# bru-breakout.net
KiCad netlist of a schematic drawn in EAGLE
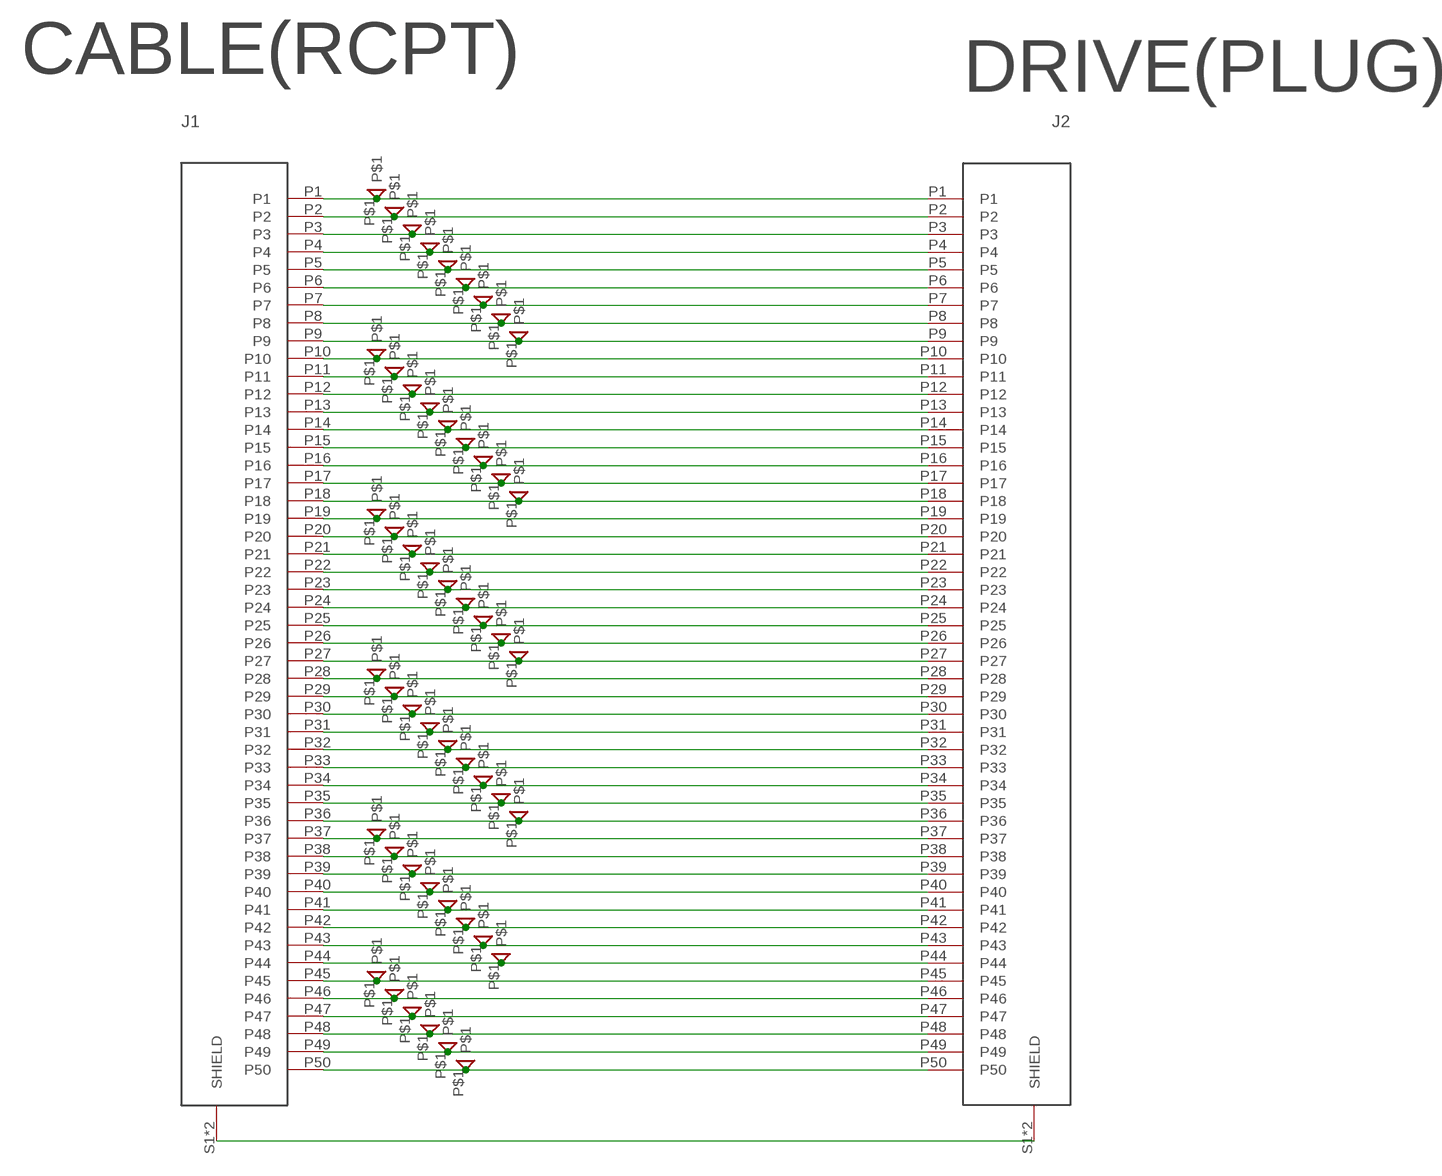
[diagram p0: schematic, sheet 1]

(export (version "E")
  (design (tool "Eeschema 10.0.6"))
  (components
    (comp (ref "J1")
      (value "3M_10250-55H3PC(RECEPTACLE)")
      (footprint "eagle-import:3M_10250-55H3PC(RECEPTACLE)")
      (libsource (lib "eagle-import") (part "3M_10250-55H3PC(RECEPTACLE)"))
    )
    (comp (ref "J2")
      (value "3M_10150-52E2PC(PLUG)")
      (footprint "eagle-import:3M_10150-52E2PC(PLUG)")
      (libsource (lib "eagle-import") (part "3M_10150-52E2PC(PLUG)"))
    )
    (comp (ref "U$1")
      (value "PTH_SMALL")
      (footprint "eagle-import:PTH_SMALL")
      (libsource (lib "eagle-import") (part "PTH_SMALL"))
    )
    (comp (ref "U$2")
      (value "PTH_SMALL")
      (footprint "eagle-import:PTH_SMALL")
      (libsource (lib "eagle-import") (part "PTH_SMALL"))
    )
    (comp (ref "U$3")
      (value "PTH_SMALL")
      (footprint "eagle-import:PTH_SMALL")
      (libsource (lib "eagle-import") (part "PTH_SMALL"))
    )
    (comp (ref "U$4")
      (value "PTH_SMALL")
      (footprint "eagle-import:PTH_SMALL")
      (libsource (lib "eagle-import") (part "PTH_SMALL"))
    )
    (comp (ref "U$5")
      (value "PTH_SMALL")
      (footprint "eagle-import:PTH_SMALL")
      (libsource (lib "eagle-import") (part "PTH_SMALL"))
    )
    (comp (ref "U$6")
      (value "PTH_SMALL")
      (footprint "eagle-import:PTH_SMALL")
      (libsource (lib "eagle-import") (part "PTH_SMALL"))
    )
    (comp (ref "U$7")
      (value "PTH_SMALL")
      (footprint "eagle-import:PTH_SMALL")
      (libsource (lib "eagle-import") (part "PTH_SMALL"))
    )
    (comp (ref "U$8")
      (value "PTH_SMALL")
      (footprint "eagle-import:PTH_SMALL")
      (libsource (lib "eagle-import") (part "PTH_SMALL"))
    )
    (comp (ref "U$9")
      (value "PTH_SMALL")
      (footprint "eagle-import:PTH_SMALL")
      (libsource (lib "eagle-import") (part "PTH_SMALL"))
    )
    (comp (ref "U$10")
      (value "PTH_SMALL")
      (footprint "eagle-import:PTH_SMALL")
      (libsource (lib "eagle-import") (part "PTH_SMALL"))
    )
    (comp (ref "U$11")
      (value "PTH_SMALL")
      (footprint "eagle-import:PTH_SMALL")
      (libsource (lib "eagle-import") (part "PTH_SMALL"))
    )
    (comp (ref "U$12")
      (value "PTH_SMALL")
      (footprint "eagle-import:PTH_SMALL")
      (libsource (lib "eagle-import") (part "PTH_SMALL"))
    )
    (comp (ref "U$13")
      (value "PTH_SMALL")
      (footprint "eagle-import:PTH_SMALL")
      (libsource (lib "eagle-import") (part "PTH_SMALL"))
    )
    (comp (ref "U$14")
      (value "PTH_SMALL")
      (footprint "eagle-import:PTH_SMALL")
      (libsource (lib "eagle-import") (part "PTH_SMALL"))
    )
    (comp (ref "U$15")
      (value "PTH_SMALL")
      (footprint "eagle-import:PTH_SMALL")
      (libsource (lib "eagle-import") (part "PTH_SMALL"))
    )
    (comp (ref "U$16")
      (value "PTH_SMALL")
      (footprint "eagle-import:PTH_SMALL")
      (libsource (lib "eagle-import") (part "PTH_SMALL"))
    )
    (comp (ref "U$17")
      (value "PTH_SMALL")
      (footprint "eagle-import:PTH_SMALL")
      (libsource (lib "eagle-import") (part "PTH_SMALL"))
    )
    (comp (ref "U$18")
      (value "PTH_SMALL")
      (footprint "eagle-import:PTH_SMALL")
      (libsource (lib "eagle-import") (part "PTH_SMALL"))
    )
    (comp (ref "U$19")
      (value "PTH_SMALL")
      (footprint "eagle-import:PTH_SMALL")
      (libsource (lib "eagle-import") (part "PTH_SMALL"))
    )
    (comp (ref "U$20")
      (value "PTH_SMALL")
      (footprint "eagle-import:PTH_SMALL")
      (libsource (lib "eagle-import") (part "PTH_SMALL"))
    )
    (comp (ref "U$21")
      (value "PTH_SMALL")
      (footprint "eagle-import:PTH_SMALL")
      (libsource (lib "eagle-import") (part "PTH_SMALL"))
    )
    (comp (ref "U$22")
      (value "PTH_SMALL")
      (footprint "eagle-import:PTH_SMALL")
      (libsource (lib "eagle-import") (part "PTH_SMALL"))
    )
    (comp (ref "U$23")
      (value "PTH_SMALL")
      (footprint "eagle-import:PTH_SMALL")
      (libsource (lib "eagle-import") (part "PTH_SMALL"))
    )
    (comp (ref "U$24")
      (value "PTH_SMALL")
      (footprint "eagle-import:PTH_SMALL")
      (libsource (lib "eagle-import") (part "PTH_SMALL"))
    )
    (comp (ref "U$25")
      (value "PTH_SMALL")
      (footprint "eagle-import:PTH_SMALL")
      (libsource (lib "eagle-import") (part "PTH_SMALL"))
    )
    (comp (ref "U$26")
      (value "PTH_SMALL")
      (footprint "eagle-import:PTH_SMALL")
      (libsource (lib "eagle-import") (part "PTH_SMALL"))
    )
    (comp (ref "U$27")
      (value "PTH_SMALL")
      (footprint "eagle-import:PTH_SMALL")
      (libsource (lib "eagle-import") (part "PTH_SMALL"))
    )
    (comp (ref "U$28")
      (value "PTH_SMALL")
      (footprint "eagle-import:PTH_SMALL")
      (libsource (lib "eagle-import") (part "PTH_SMALL"))
    )
    (comp (ref "U$29")
      (value "PTH_SMALL")
      (footprint "eagle-import:PTH_SMALL")
      (libsource (lib "eagle-import") (part "PTH_SMALL"))
    )
    (comp (ref "U$30")
      (value "PTH_SMALL")
      (footprint "eagle-import:PTH_SMALL")
      (libsource (lib "eagle-import") (part "PTH_SMALL"))
    )
    (comp (ref "U$31")
      (value "PTH_SMALL")
      (footprint "eagle-import:PTH_SMALL")
      (libsource (lib "eagle-import") (part "PTH_SMALL"))
    )
    (comp (ref "U$32")
      (value "PTH_SMALL")
      (footprint "eagle-import:PTH_SMALL")
      (libsource (lib "eagle-import") (part "PTH_SMALL"))
    )
    (comp (ref "U$33")
      (value "PTH_SMALL")
      (footprint "eagle-import:PTH_SMALL")
      (libsource (lib "eagle-import") (part "PTH_SMALL"))
    )
    (comp (ref "U$34")
      (value "PTH_SMALL")
      (footprint "eagle-import:PTH_SMALL")
      (libsource (lib "eagle-import") (part "PTH_SMALL"))
    )
    (comp (ref "U$35")
      (value "PTH_SMALL")
      (footprint "eagle-import:PTH_SMALL")
      (libsource (lib "eagle-import") (part "PTH_SMALL"))
    )
    (comp (ref "U$36")
      (value "PTH_SMALL")
      (footprint "eagle-import:PTH_SMALL")
      (libsource (lib "eagle-import") (part "PTH_SMALL"))
    )
    (comp (ref "U$37")
      (value "PTH_SMALL")
      (footprint "eagle-import:PTH_SMALL")
      (libsource (lib "eagle-import") (part "PTH_SMALL"))
    )
    (comp (ref "U$38")
      (value "PTH_SMALL")
      (footprint "eagle-import:PTH_SMALL")
      (libsource (lib "eagle-import") (part "PTH_SMALL"))
    )
    (comp (ref "U$39")
      (value "PTH_SMALL")
      (footprint "eagle-import:PTH_SMALL")
      (libsource (lib "eagle-import") (part "PTH_SMALL"))
    )
    (comp (ref "U$40")
      (value "PTH_SMALL")
      (footprint "eagle-import:PTH_SMALL")
      (libsource (lib "eagle-import") (part "PTH_SMALL"))
    )
    (comp (ref "U$41")
      (value "PTH_SMALL")
      (footprint "eagle-import:PTH_SMALL")
      (libsource (lib "eagle-import") (part "PTH_SMALL"))
    )
    (comp (ref "U$42")
      (value "PTH_SMALL")
      (footprint "eagle-import:PTH_SMALL")
      (libsource (lib "eagle-import") (part "PTH_SMALL"))
    )
    (comp (ref "U$43")
      (value "PTH_SMALL")
      (footprint "eagle-import:PTH_SMALL")
      (libsource (lib "eagle-import") (part "PTH_SMALL"))
    )
    (comp (ref "U$44")
      (value "PTH_SMALL")
      (footprint "eagle-import:PTH_SMALL")
      (libsource (lib "eagle-import") (part "PTH_SMALL"))
    )
    (comp (ref "U$45")
      (value "PTH_SMALL")
      (footprint "eagle-import:PTH_SMALL")
      (libsource (lib "eagle-import") (part "PTH_SMALL"))
    )
    (comp (ref "U$46")
      (value "PTH_SMALL")
      (footprint "eagle-import:PTH_SMALL")
      (libsource (lib "eagle-import") (part "PTH_SMALL"))
    )
    (comp (ref "U$47")
      (value "PTH_SMALL")
      (footprint "eagle-import:PTH_SMALL")
      (libsource (lib "eagle-import") (part "PTH_SMALL"))
    )
    (comp (ref "U$48")
      (value "PTH_SMALL")
      (footprint "eagle-import:PTH_SMALL")
      (libsource (lib "eagle-import") (part "PTH_SMALL"))
    )
    (comp (ref "U$49")
      (value "PTH_SMALL")
      (footprint "eagle-import:PTH_SMALL")
      (libsource (lib "eagle-import") (part "PTH_SMALL"))
    )
    (comp (ref "U$50")
      (value "PTH_SMALL")
      (footprint "eagle-import:PTH_SMALL")
      (libsource (lib "eagle-import") (part "PTH_SMALL"))
    )
  )
  (nets
    (net (code "1") (name "Net-(J1-PadP1)") (class "Default")
      (node (ref "J1") (pin "P1") (pinfunction "P1_P1") (pintype "bidirectional"))
      (node (ref "J2") (pin "P1") (pinfunction "P1_P1") (pintype "bidirectional"))
      (node (ref "U$1") (pin "P$1") (pinfunction "P$1_P$1") (pintype "bidirectional"))
    )
    (net (code "2") (name "Net-(J1-PadP2)") (class "Default")
      (node (ref "J1") (pin "P2") (pinfunction "P2_P2") (pintype "bidirectional"))
      (node (ref "J2") (pin "P2") (pinfunction "P2_P2") (pintype "bidirectional"))
      (node (ref "U$2") (pin "P$1") (pinfunction "P$1_P$1") (pintype "bidirectional"))
    )
    (net (code "3") (name "Net-(J1-PadP3)") (class "Default")
      (node (ref "J1") (pin "P3") (pinfunction "P3_P3") (pintype "bidirectional"))
      (node (ref "J2") (pin "P3") (pinfunction "P3_P3") (pintype "bidirectional"))
      (node (ref "U$3") (pin "P$1") (pinfunction "P$1_P$1") (pintype "bidirectional"))
    )
    (net (code "4") (name "Net-(J1-PadP4)") (class "Default")
      (node (ref "J1") (pin "P4") (pinfunction "P4_P4") (pintype "bidirectional"))
      (node (ref "J2") (pin "P4") (pinfunction "P4_P4") (pintype "bidirectional"))
      (node (ref "U$4") (pin "P$1") (pinfunction "P$1_P$1") (pintype "bidirectional"))
    )
    (net (code "5") (name "Net-(J1-PadP5)") (class "Default")
      (node (ref "J1") (pin "P5") (pinfunction "P5_P5") (pintype "bidirectional"))
      (node (ref "J2") (pin "P5") (pinfunction "P5_P5") (pintype "bidirectional"))
      (node (ref "U$5") (pin "P$1") (pinfunction "P$1_P$1") (pintype "bidirectional"))
    )
    (net (code "6") (name "Net-(J1-PadP6)") (class "Default")
      (node (ref "J1") (pin "P6") (pinfunction "P6_P6") (pintype "bidirectional"))
      (node (ref "J2") (pin "P6") (pinfunction "P6_P6") (pintype "bidirectional"))
      (node (ref "U$6") (pin "P$1") (pinfunction "P$1_P$1") (pintype "bidirectional"))
    )
    (net (code "7") (name "Net-(J1-PadP7)") (class "Default")
      (node (ref "J1") (pin "P7") (pinfunction "P7_P7") (pintype "bidirectional"))
      (node (ref "J2") (pin "P7") (pinfunction "P7_P7") (pintype "bidirectional"))
      (node (ref "U$7") (pin "P$1") (pinfunction "P$1_P$1") (pintype "bidirectional"))
    )
    (net (code "8") (name "Net-(J1-PadP8)") (class "Default")
      (node (ref "J1") (pin "P8") (pinfunction "P8_P8") (pintype "bidirectional"))
      (node (ref "J2") (pin "P8") (pinfunction "P8_P8") (pintype "bidirectional"))
      (node (ref "U$8") (pin "P$1") (pinfunction "P$1_P$1") (pintype "bidirectional"))
    )
    (net (code "9") (name "Net-(J1-PadP9)") (class "Default")
      (node (ref "J1") (pin "P9") (pinfunction "P9_P9") (pintype "bidirectional"))
      (node (ref "J2") (pin "P9") (pinfunction "P9_P9") (pintype "bidirectional"))
      (node (ref "U$9") (pin "P$1") (pinfunction "P$1_P$1") (pintype "bidirectional"))
    )
    (net (code "10") (name "Net-(J1-PadP10)") (class "Default")
      (node (ref "J1") (pin "P10") (pinfunction "P10_P10") (pintype "bidirectional"))
      (node (ref "J2") (pin "P10") (pinfunction "P10_P10") (pintype "bidirectional"))
      (node (ref "U$10") (pin "P$1") (pinfunction "P$1_P$1") (pintype "bidirectional"))
    )
    (net (code "11") (name "Net-(J1-PadP11)") (class "Default")
      (node (ref "J1") (pin "P11") (pinfunction "P11_P11") (pintype "bidirectional"))
      (node (ref "J2") (pin "P11") (pinfunction "P11_P11") (pintype "bidirectional"))
      (node (ref "U$11") (pin "P$1") (pinfunction "P$1_P$1") (pintype "bidirectional"))
    )
    (net (code "12") (name "Net-(J1-PadP12)") (class "Default")
      (node (ref "J1") (pin "P12") (pinfunction "P12_P12") (pintype "bidirectional"))
      (node (ref "J2") (pin "P12") (pinfunction "P12_P12") (pintype "bidirectional"))
      (node (ref "U$12") (pin "P$1") (pinfunction "P$1_P$1") (pintype "bidirectional"))
    )
    (net (code "13") (name "Net-(J1-PadP13)") (class "Default")
      (node (ref "J1") (pin "P13") (pinfunction "P13_P13") (pintype "bidirectional"))
      (node (ref "J2") (pin "P13") (pinfunction "P13_P13") (pintype "bidirectional"))
      (node (ref "U$13") (pin "P$1") (pinfunction "P$1_P$1") (pintype "bidirectional"))
    )
    (net (code "14") (name "Net-(J1-PadP14)") (class "Default")
      (node (ref "J1") (pin "P14") (pinfunction "P14_P14") (pintype "bidirectional"))
      (node (ref "J2") (pin "P14") (pinfunction "P14_P14") (pintype "bidirectional"))
      (node (ref "U$14") (pin "P$1") (pinfunction "P$1_P$1") (pintype "bidirectional"))
    )
    (net (code "15") (name "Net-(J1-PadP15)") (class "Default")
      (node (ref "J1") (pin "P15") (pinfunction "P15_P15") (pintype "bidirectional"))
      (node (ref "J2") (pin "P15") (pinfunction "P15_P15") (pintype "bidirectional"))
      (node (ref "U$15") (pin "P$1") (pinfunction "P$1_P$1") (pintype "bidirectional"))
    )
    (net (code "16") (name "Net-(J1-PadP16)") (class "Default")
      (node (ref "J1") (pin "P16") (pinfunction "P16_P16") (pintype "bidirectional"))
      (node (ref "J2") (pin "P16") (pinfunction "P16_P16") (pintype "bidirectional"))
      (node (ref "U$16") (pin "P$1") (pinfunction "P$1_P$1") (pintype "bidirectional"))
    )
    (net (code "17") (name "Net-(J1-PadP17)") (class "Default")
      (node (ref "J1") (pin "P17") (pinfunction "P17_P17") (pintype "bidirectional"))
      (node (ref "J2") (pin "P17") (pinfunction "P17_P17") (pintype "bidirectional"))
      (node (ref "U$17") (pin "P$1") (pinfunction "P$1_P$1") (pintype "bidirectional"))
    )
    (net (code "18") (name "Net-(J1-PadP18)") (class "Default")
      (node (ref "J1") (pin "P18") (pinfunction "P18_P18") (pintype "bidirectional"))
      (node (ref "J2") (pin "P18") (pinfunction "P18_P18") (pintype "bidirectional"))
      (node (ref "U$18") (pin "P$1") (pinfunction "P$1_P$1") (pintype "bidirectional"))
    )
    (net (code "19") (name "Net-(J1-PadP19)") (class "Default")
      (node (ref "J1") (pin "P19") (pinfunction "P19_P19") (pintype "bidirectional"))
      (node (ref "J2") (pin "P19") (pinfunction "P19_P19") (pintype "bidirectional"))
      (node (ref "U$19") (pin "P$1") (pinfunction "P$1_P$1") (pintype "bidirectional"))
    )
    (net (code "20") (name "Net-(J1-PadP20)") (class "Default")
      (node (ref "J1") (pin "P20") (pinfunction "P20_P20") (pintype "bidirectional"))
      (node (ref "J2") (pin "P20") (pinfunction "P20_P20") (pintype "bidirectional"))
      (node (ref "U$20") (pin "P$1") (pinfunction "P$1_P$1") (pintype "bidirectional"))
    )
    (net (code "21") (name "Net-(J1-PadP21)") (class "Default")
      (node (ref "J1") (pin "P21") (pinfunction "P21_P21") (pintype "bidirectional"))
      (node (ref "J2") (pin "P21") (pinfunction "P21_P21") (pintype "bidirectional"))
      (node (ref "U$21") (pin "P$1") (pinfunction "P$1_P$1") (pintype "bidirectional"))
    )
    (net (code "22") (name "Net-(J1-PadP22)") (class "Default")
      (node (ref "J1") (pin "P22") (pinfunction "P22_P22") (pintype "bidirectional"))
      (node (ref "J2") (pin "P22") (pinfunction "P22_P22") (pintype "bidirectional"))
      (node (ref "U$22") (pin "P$1") (pinfunction "P$1_P$1") (pintype "bidirectional"))
    )
    (net (code "23") (name "Net-(J1-PadP23)") (class "Default")
      (node (ref "J1") (pin "P23") (pinfunction "P23_P23") (pintype "bidirectional"))
      (node (ref "J2") (pin "P23") (pinfunction "P23_P23") (pintype "bidirectional"))
      (node (ref "U$23") (pin "P$1") (pinfunction "P$1_P$1") (pintype "bidirectional"))
    )
    (net (code "24") (name "Net-(J1-PadP24)") (class "Default")
      (node (ref "J1") (pin "P24") (pinfunction "P24_P24") (pintype "bidirectional"))
      (node (ref "J2") (pin "P24") (pinfunction "P24_P24") (pintype "bidirectional"))
      (node (ref "U$24") (pin "P$1") (pinfunction "P$1_P$1") (pintype "bidirectional"))
    )
    (net (code "25") (name "Net-(J1-PadP25)") (class "Default")
      (node (ref "J1") (pin "P25") (pinfunction "P25_P25") (pintype "bidirectional"))
      (node (ref "J2") (pin "P25") (pinfunction "P25_P25") (pintype "bidirectional"))
      (node (ref "U$25") (pin "P$1") (pinfunction "P$1_P$1") (pintype "bidirectional"))
    )
    (net (code "26") (name "Net-(J1-PadP26)") (class "Default")
      (node (ref "J1") (pin "P26") (pinfunction "P26_P26") (pintype "bidirectional"))
      (node (ref "J2") (pin "P26") (pinfunction "P26_P26") (pintype "bidirectional"))
      (node (ref "U$26") (pin "P$1") (pinfunction "P$1_P$1") (pintype "bidirectional"))
    )
    (net (code "27") (name "Net-(J1-PadP27)") (class "Default")
      (node (ref "J1") (pin "P27") (pinfunction "P27_P27") (pintype "bidirectional"))
      (node (ref "J2") (pin "P27") (pinfunction "P27_P27") (pintype "bidirectional"))
      (node (ref "U$27") (pin "P$1") (pinfunction "P$1_P$1") (pintype "bidirectional"))
    )
    (net (code "28") (name "Net-(J1-PadP28)") (class "Default")
      (node (ref "J1") (pin "P28") (pinfunction "P28_P28") (pintype "bidirectional"))
      (node (ref "J2") (pin "P28") (pinfunction "P28_P28") (pintype "bidirectional"))
      (node (ref "U$28") (pin "P$1") (pinfunction "P$1_P$1") (pintype "bidirectional"))
    )
    (net (code "29") (name "Net-(J1-PadP29)") (class "Default")
      (node (ref "J1") (pin "P29") (pinfunction "P29_P29") (pintype "bidirectional"))
      (node (ref "J2") (pin "P29") (pinfunction "P29_P29") (pintype "bidirectional"))
      (node (ref "U$29") (pin "P$1") (pinfunction "P$1_P$1") (pintype "bidirectional"))
    )
    (net (code "30") (name "Net-(J1-PadP30)") (class "Default")
      (node (ref "J1") (pin "P30") (pinfunction "P30_P30") (pintype "bidirectional"))
      (node (ref "J2") (pin "P30") (pinfunction "P30_P30") (pintype "bidirectional"))
      (node (ref "U$30") (pin "P$1") (pinfunction "P$1_P$1") (pintype "bidirectional"))
    )
    (net (code "31") (name "Net-(J1-PadP31)") (class "Default")
      (node (ref "J1") (pin "P31") (pinfunction "P31_P31") (pintype "bidirectional"))
      (node (ref "J2") (pin "P31") (pinfunction "P31_P31") (pintype "bidirectional"))
      (node (ref "U$31") (pin "P$1") (pinfunction "P$1_P$1") (pintype "bidirectional"))
    )
    (net (code "32") (name "Net-(J1-PadP32)") (class "Default")
      (node (ref "J1") (pin "P32") (pinfunction "P32_P32") (pintype "bidirectional"))
      (node (ref "J2") (pin "P32") (pinfunction "P32_P32") (pintype "bidirectional"))
      (node (ref "U$32") (pin "P$1") (pinfunction "P$1_P$1") (pintype "bidirectional"))
    )
    (net (code "33") (name "Net-(J1-PadP33)") (class "Default")
      (node (ref "J1") (pin "P33") (pinfunction "P33_P33") (pintype "bidirectional"))
      (node (ref "J2") (pin "P33") (pinfunction "P33_P33") (pintype "bidirectional"))
      (node (ref "U$33") (pin "P$1") (pinfunction "P$1_P$1") (pintype "bidirectional"))
    )
    (net (code "34") (name "Net-(J1-PadP34)") (class "Default")
      (node (ref "J1") (pin "P34") (pinfunction "P34_P34") (pintype "bidirectional"))
      (node (ref "J2") (pin "P34") (pinfunction "P34_P34") (pintype "bidirectional"))
      (node (ref "U$34") (pin "P$1") (pinfunction "P$1_P$1") (pintype "bidirectional"))
    )
    (net (code "35") (name "Net-(J1-PadP35)") (class "Default")
      (node (ref "J1") (pin "P35") (pinfunction "P35_P35") (pintype "bidirectional"))
      (node (ref "J2") (pin "P35") (pinfunction "P35_P35") (pintype "bidirectional"))
      (node (ref "U$35") (pin "P$1") (pinfunction "P$1_P$1") (pintype "bidirectional"))
    )
    (net (code "36") (name "Net-(J1-PadP36)") (class "Default")
      (node (ref "J1") (pin "P36") (pinfunction "P36_P36") (pintype "bidirectional"))
      (node (ref "J2") (pin "P36") (pinfunction "P36_P36") (pintype "bidirectional"))
      (node (ref "U$36") (pin "P$1") (pinfunction "P$1_P$1") (pintype "bidirectional"))
    )
    (net (code "37") (name "Net-(J1-PadP37)") (class "Default")
      (node (ref "J1") (pin "P37") (pinfunction "P37_P37") (pintype "bidirectional"))
      (node (ref "J2") (pin "P37") (pinfunction "P37_P37") (pintype "bidirectional"))
      (node (ref "U$37") (pin "P$1") (pinfunction "P$1_P$1") (pintype "bidirectional"))
    )
    (net (code "38") (name "Net-(J1-PadP38)") (class "Default")
      (node (ref "J1") (pin "P38") (pinfunction "P38_P38") (pintype "bidirectional"))
      (node (ref "J2") (pin "P38") (pinfunction "P38_P38") (pintype "bidirectional"))
      (node (ref "U$38") (pin "P$1") (pinfunction "P$1_P$1") (pintype "bidirectional"))
    )
    (net (code "39") (name "Net-(J1-PadP39)") (class "Default")
      (node (ref "J1") (pin "P39") (pinfunction "P39_P39") (pintype "bidirectional"))
      (node (ref "J2") (pin "P39") (pinfunction "P39_P39") (pintype "bidirectional"))
      (node (ref "U$39") (pin "P$1") (pinfunction "P$1_P$1") (pintype "bidirectional"))
    )
    (net (code "40") (name "Net-(J1-PadP40)") (class "Default")
      (node (ref "J1") (pin "P40") (pinfunction "P40_P40") (pintype "bidirectional"))
      (node (ref "J2") (pin "P40") (pinfunction "P40_P40") (pintype "bidirectional"))
      (node (ref "U$40") (pin "P$1") (pinfunction "P$1_P$1") (pintype "bidirectional"))
    )
    (net (code "41") (name "Net-(J1-PadP41)") (class "Default")
      (node (ref "J1") (pin "P41") (pinfunction "P41_P41") (pintype "bidirectional"))
      (node (ref "J2") (pin "P41") (pinfunction "P41_P41") (pintype "bidirectional"))
      (node (ref "U$41") (pin "P$1") (pinfunction "P$1_P$1") (pintype "bidirectional"))
    )
    (net (code "42") (name "Net-(J1-PadP42)") (class "Default")
      (node (ref "J1") (pin "P42") (pinfunction "P42_P42") (pintype "bidirectional"))
      (node (ref "J2") (pin "P42") (pinfunction "P42_P42") (pintype "bidirectional"))
      (node (ref "U$42") (pin "P$1") (pinfunction "P$1_P$1") (pintype "bidirectional"))
    )
    (net (code "43") (name "Net-(J1-PadP43)") (class "Default")
      (node (ref "J1") (pin "P43") (pinfunction "P43_P43") (pintype "bidirectional"))
      (node (ref "J2") (pin "P43") (pinfunction "P43_P43") (pintype "bidirectional"))
      (node (ref "U$43") (pin "P$1") (pinfunction "P$1_P$1") (pintype "bidirectional"))
    )
    (net (code "44") (name "Net-(J1-PadP44)") (class "Default")
      (node (ref "J1") (pin "P44") (pinfunction "P44_P44") (pintype "bidirectional"))
      (node (ref "J2") (pin "P44") (pinfunction "P44_P44") (pintype "bidirectional"))
      (node (ref "U$44") (pin "P$1") (pinfunction "P$1_P$1") (pintype "bidirectional"))
    )
    (net (code "45") (name "Net-(J1-PadP45)") (class "Default")
      (node (ref "J1") (pin "P45") (pinfunction "P45_P45") (pintype "bidirectional"))
      (node (ref "J2") (pin "P45") (pinfunction "P45_P45") (pintype "bidirectional"))
      (node (ref "U$45") (pin "P$1") (pinfunction "P$1_P$1") (pintype "bidirectional"))
    )
    (net (code "46") (name "Net-(J1-PadP46)") (class "Default")
      (node (ref "J1") (pin "P46") (pinfunction "P46_P46") (pintype "bidirectional"))
      (node (ref "J2") (pin "P46") (pinfunction "P46_P46") (pintype "bidirectional"))
      (node (ref "U$46") (pin "P$1") (pinfunction "P$1_P$1") (pintype "bidirectional"))
    )
    (net (code "47") (name "Net-(J1-PadP47)") (class "Default")
      (node (ref "J1") (pin "P47") (pinfunction "P47_P47") (pintype "bidirectional"))
      (node (ref "J2") (pin "P47") (pinfunction "P47_P47") (pintype "bidirectional"))
      (node (ref "U$47") (pin "P$1") (pinfunction "P$1_P$1") (pintype "bidirectional"))
    )
    (net (code "48") (name "Net-(J1-PadP48)") (class "Default")
      (node (ref "J1") (pin "P48") (pinfunction "P48_P48") (pintype "bidirectional"))
      (node (ref "J2") (pin "P48") (pinfunction "P48_P48") (pintype "bidirectional"))
      (node (ref "U$48") (pin "P$1") (pinfunction "P$1_P$1") (pintype "bidirectional"))
    )
    (net (code "49") (name "Net-(J1-PadP49)") (class "Default")
      (node (ref "J1") (pin "P49") (pinfunction "P49_P49") (pintype "bidirectional"))
      (node (ref "J2") (pin "P49") (pinfunction "P49_P49") (pintype "bidirectional"))
      (node (ref "U$49") (pin "P$1") (pinfunction "P$1_P$1") (pintype "bidirectional"))
    )
    (net (code "50") (name "Net-(J1-PadP50)") (class "Default")
      (node (ref "J1") (pin "P50") (pinfunction "P50_P50") (pintype "bidirectional"))
      (node (ref "J2") (pin "P50") (pinfunction "P50_P50") (pintype "bidirectional"))
      (node (ref "U$50") (pin "P$1") (pinfunction "P$1_P$1") (pintype "bidirectional"))
    )
    (net (code "51") (name "Net-(J1-SHIELD-PadS1)") (class "Default")
      (node (ref "J1") (pin "S1") (pinfunction "SHIELD_S1") (pintype "bidirectional"))
      (node (ref "J1") (pin "S2") (pinfunction "SHIELD_S2") (pintype "bidirectional"))
      (node (ref "J2") (pin "S1") (pinfunction "SHIELD_S1") (pintype "bidirectional"))
      (node (ref "J2") (pin "S2") (pinfunction "SHIELD_S2") (pintype "bidirectional"))
    )
  )
)
